# TSC_AD7843.net
KiCad netlist of a schematic drawn in Altium Designer
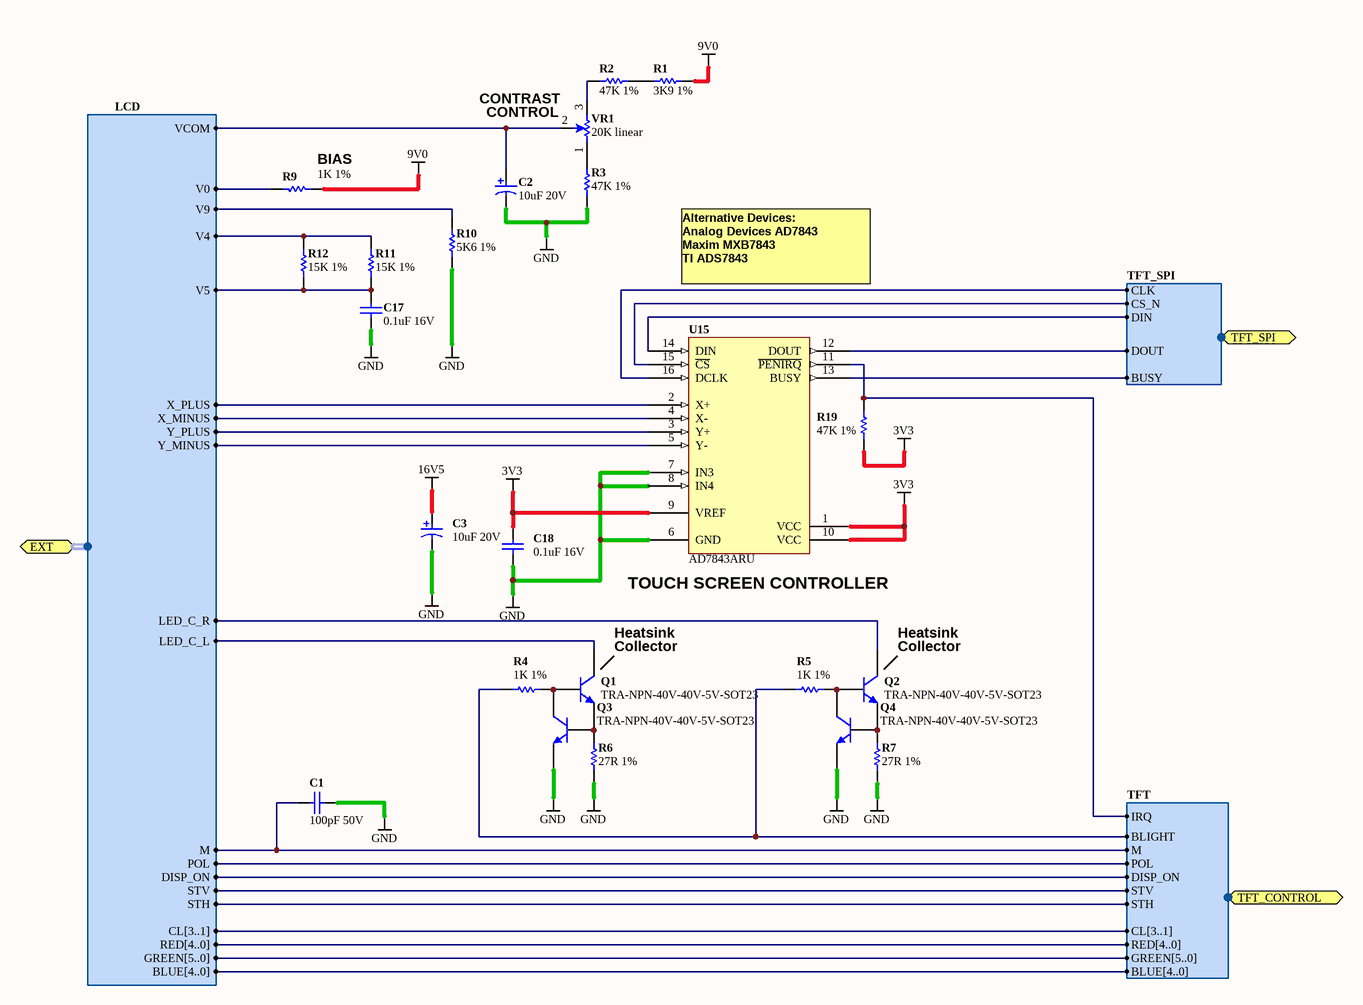
[diagram p0: TSC_AD7843.SchDoc]

(export (version "E")
  (design (tool "Eeschema 10.0.6"))
  (components
    (comp (ref "C1")
      (value "100pF 50V")
      (footprint "CAPC1005-STAR")
      (description "Capacitor, Ceramic, 100pF 5% 50V 0402 (1005) COG")
      (fields (field (name "TOLERANCE") "5 %"))
      (libsource (lib "altium-import") (part "root_3_mirrored_CAP-NP_"))
    )
    (comp (ref "C2")
      (value "10uF 20V")
      (footprint "CAPC3528-STAR")
      (description "Capacitor, Tantalum, 10uF 10% 20V MCCT-B (3528)")
      (fields (field (name "TOLERANCE") "10 %"))
      (libsource (lib "altium-import") (part "root_0_CAP-P_"))
    )
    (comp (ref "C3")
      (value "10uF 20V")
      (footprint "CAPC3528-STAR")
      (description "Capacitor, Tantalum, 10uF 10% 20V MCCT-B (3528)")
      (fields (field (name "TOLERANCE") "10 %"))
      (libsource (lib "altium-import") (part "root_0_CAP-P_"))
    )
    (comp (ref "C17")
      (value "0.1uF 16V")
      (footprint "CAPC1005-STAR")
      (description "Capacitor, Ceramic, 0.1uF 10% 16V 0402 (1005) X7R")
      (fields (field (name "TOLERANCE") "10 %"))
      (libsource (lib "altium-import") (part "root_0_mirrored_CAP-NP_"))
    )
    (comp (ref "C18")
      (value "0.1uF 16V")
      (footprint "CAPC1005-STAR")
      (description "Capacitor, Ceramic, 0.1uF 10% 16V 0402 (1005) X7R")
      (fields (field (name "TOLERANCE") "10 %"))
      (libsource (lib "altium-import") (part "root_0_CAP-NP_"))
    )
    (comp (ref "Q1")
      (value "TRA-NPN-40V-40V-5V-SOT23")
      (footprint "SOT95P230-3C")
      (description "Transistor, FMMT491A Small Signal NPN")
      (libsource (lib "altium-import") (part "root_0_TRA-NPN_"))
    )
    (comp (ref "Q2")
      (value "TRA-NPN-40V-40V-5V-SOT23")
      (footprint "SOT95P230-3C")
      (description "Transistor, FMMT491A Small Signal NPN")
      (libsource (lib "altium-import") (part "root_0_TRA-NPN_"))
    )
    (comp (ref "Q3")
      (value "TRA-NPN-40V-40V-5V-SOT23")
      (footprint "SOT95P230-3C")
      (description "Transistor, FMMT491A Small Signal NPN")
      (libsource (lib "altium-import") (part "root_0_mirrored_TRA-NPN_"))
    )
    (comp (ref "Q4")
      (value "TRA-NPN-40V-40V-5V-SOT23")
      (footprint "SOT95P230-3C")
      (description "Transistor, FMMT491A Small Signal NPN")
      (libsource (lib "altium-import") (part "root_0_mirrored_TRA-NPN_"))
    )
    (comp (ref "R1")
      (value "3K9 1%")
      (footprint "RESC1005-STAR")
      (description "Resistor, 3K9 1% 0402 (1005)")
      (fields (field (name "TOLERANCE") "1 %"))
      (libsource (lib "altium-import") (part "root_1_RES_"))
    )
    (comp (ref "R2")
      (value "47K 1%")
      (footprint "RESC1005-STAR")
      (description "Resistor, 47K 1% 0402 (1005)")
      (fields (field (name "TOLERANCE") "1 %"))
      (libsource (lib "altium-import") (part "root_1_RES_"))
    )
    (comp (ref "R3")
      (value "47K 1%")
      (footprint "RESC1005-STAR")
      (description "Resistor, 47K 1% 0402 (1005)")
      (fields (field (name "TOLERANCE") "1 %"))
      (libsource (lib "altium-import") (part "root_2_RES_"))
    )
    (comp (ref "R4")
      (value "1K 1%")
      (footprint "RESC1005-STAR")
      (description "Resistor, 1K 1% 0402 (1005)")
      (fields (field (name "TOLERANCE") "1 %"))
      (libsource (lib "altium-import") (part "root_1_RES_"))
    )
    (comp (ref "R5")
      (value "1K 1%")
      (footprint "RESC1005-STAR")
      (description "Resistor, 1K 1% 0402 (1005)")
      (fields (field (name "TOLERANCE") "1 %"))
      (libsource (lib "altium-import") (part "root_1_RES_"))
    )
    (comp (ref "R6")
      (value "27R 1%")
      (footprint "RESC1005-STAR")
      (description "Resistor, 27R 1% 0402 (1005)")
      (fields (field (name "TOLERANCE") "1 %"))
      (libsource (lib "altium-import") (part "root_2_RES_"))
    )
    (comp (ref "R7")
      (value "27R 1%")
      (footprint "RESC1005-STAR")
      (description "Resistor, 27R 1% 0402 (1005)")
      (fields (field (name "TOLERANCE") "1 %"))
      (libsource (lib "altium-import") (part "root_2_RES_"))
    )
    (comp (ref "R9")
      (value "1K 1%")
      (footprint "RESC1005-STAR")
      (description "Resistor, 1K 1% 0402 (1005)")
      (fields (field (name "TOLERANCE") "1 %"))
      (libsource (lib "altium-import") (part "root_3_mirrored_RES_"))
    )
    (comp (ref "R10")
      (value "5K6 1%")
      (footprint "RESC1005-STAR")
      (description "Resistor, 5K6 1% 0402 (1005)")
      (fields (field (name "TOLERANCE") "1 %"))
      (libsource (lib "altium-import") (part "root_2_RES_"))
    )
    (comp (ref "R11")
      (value "15K 1%")
      (footprint "RESC1005-STAR")
      (description "Resistor, 15K 1% 0402 (1005)")
      (fields (field (name "TOLERANCE") "1 %"))
      (libsource (lib "altium-import") (part "root_2_RES_"))
    )
    (comp (ref "R12")
      (value "15K 1%")
      (footprint "RESC1005-STAR")
      (description "Resistor, 15K 1% 0402 (1005)")
      (fields (field (name "TOLERANCE") "1 %"))
      (libsource (lib "altium-import") (part "root_2_RES_"))
    )
    (comp (ref "R19")
      (value "47K 1%")
      (footprint "RESC1005-STAR")
      (description "Resistor, 47K 1% 0402 (1005)")
      (fields (field (name "TOLERANCE") "1 %"))
      (libsource (lib "altium-import") (part "root_0_RES_"))
    )
    (comp (ref "U15")
      (value "AD7843ARU")
      (footprint "TSOP65P638-16")
      (description "AD7843ARU,12-bit SPI Touch Screen Digitizer")
      (libsource (lib "altium-import") (part "root_0_AD7843ARU_"))
    )
    (comp (ref "VR1")
      (value "20K linear")
      (footprint "TRIM_3314J-1-203E")
      (description "Potentiometer, 20K 4mm Cermet PCB SMT Trimmer")
      (libsource (lib "altium-import") (part "root_2_mirrored_POT_"))
    )
  )
  (nets
    (net (code "5") (name "/BLIGHT") (class "Default")
      (node (ref "R4") (pin "1") (pinfunction "1_1") (pintype "passive"))
      (node (ref "R5") (pin "1") (pinfunction "1_1") (pintype "passive"))
    )
    (net (code "6") (name "/BUSY") (class "Default")
      (node (ref "U15") (pin "13") (pinfunction "BUSY_13") (pintype "output"))
    )
    (net (code "7") (name "/CLK") (class "Default")
      (node (ref "U15") (pin "16") (pinfunction "DCLK_16") (pintype "input"))
    )
    (net (code "8") (name "/CS_N") (class "Default")
      (node (ref "U15") (pin "15") (pinfunction "~{CS}_15") (pintype "input"))
    )
    (net (code "9") (name "/DIN") (class "Default")
      (node (ref "U15") (pin "14") (pinfunction "DIN_14") (pintype "input"))
    )
    (net (code "11") (name "/DOUT") (class "Default")
      (node (ref "U15") (pin "12") (pinfunction "DOUT_12") (pintype "output"))
    )
    (net (code "12") (name "/IRQ") (class "Default")
      (node (ref "R19") (pin "1") (pinfunction "1_1") (pintype "passive"))
      (node (ref "U15") (pin "11") (pinfunction "~{PENIRQ}_11") (pintype "output"))
    )
    (net (code "13") (name "/LED_C_L") (class "Default")
      (node (ref "Q1") (pin "3") (pinfunction "C_3") (pintype "passive"))
    )
    (net (code "14") (name "/LED_C_R") (class "Default")
      (node (ref "Q2") (pin "3") (pinfunction "C_3") (pintype "passive"))
    )
    (net (code "15") (name "/M") (class "Default")
      (node (ref "C1") (pin "1") (pinfunction "1_1") (pintype "passive"))
    )
    (net (code "20") (name "/V0") (class "Default")
      (node (ref "R9") (pin "1") (pinfunction "1_1") (pintype "passive"))
    )
    (net (code "21") (name "/V4") (class "Default")
      (node (ref "R11") (pin "2") (pinfunction "2_2") (pintype "passive"))
      (node (ref "R12") (pin "2") (pinfunction "2_2") (pintype "passive"))
    )
    (net (code "22") (name "/V5") (class "Default")
      (node (ref "C17") (pin "1") (pinfunction "1_1") (pintype "passive"))
      (node (ref "R11") (pin "1") (pinfunction "1_1") (pintype "passive"))
      (node (ref "R12") (pin "1") (pinfunction "1_1") (pintype "passive"))
    )
    (net (code "23") (name "/V9") (class "Default")
      (node (ref "R10") (pin "2") (pinfunction "2_2") (pintype "passive"))
    )
    (net (code "24") (name "/VCOM") (class "Default")
      (node (ref "C2") (pin "1") (pinfunction "1_1") (pintype "passive"))
      (node (ref "VR1") (pin "2") (pinfunction "2_2") (pintype "passive"))
    )
    (net (code "25") (name "/X_MINUS") (class "Default")
      (node (ref "U15") (pin "4") (pinfunction "X-_4") (pintype "input"))
    )
    (net (code "26") (name "/X_PLUS") (class "Default")
      (node (ref "U15") (pin "2") (pinfunction "X+_2") (pintype "input"))
    )
    (net (code "27") (name "/Y_MINUS") (class "Default")
      (node (ref "U15") (pin "5") (pinfunction "Y-_5") (pintype "input"))
    )
    (net (code "28") (name "/Y_PLUS") (class "Default")
      (node (ref "U15") (pin "3") (pinfunction "Y+_3") (pintype "input"))
    )
    (net (code "32") (name "3V3") (class "Default")
      (node (ref "C18") (pin "1") (pinfunction "1_1") (pintype "passive"))
      (node (ref "R19") (pin "2") (pinfunction "2_2") (pintype "passive"))
      (node (ref "U15") (pin "1") (pinfunction "VCC_1") (pintype "power_in"))
      (node (ref "U15") (pin "10") (pinfunction "VCC_10") (pintype "power_in"))
      (node (ref "U15") (pin "9") (pinfunction "VREF_9") (pintype "passive"))
    )
    (net (code "33") (name "9V0") (class "Default")
      (node (ref "R1") (pin "2") (pinfunction "2_2") (pintype "passive"))
      (node (ref "R9") (pin "2") (pinfunction "2_2") (pintype "passive"))
    )
    (net (code "34") (name "16V5") (class "Default")
      (node (ref "C3") (pin "1") (pinfunction "1_1") (pintype "passive"))
    )
    (net (code "35") (name "GND") (class "Default")
      (node (ref "C1") (pin "2") (pinfunction "2_2") (pintype "passive"))
      (node (ref "C17") (pin "2") (pinfunction "2_2") (pintype "passive"))
      (node (ref "C18") (pin "2") (pinfunction "2_2") (pintype "passive"))
      (node (ref "C2") (pin "2") (pinfunction "2_2") (pintype "passive"))
      (node (ref "C3") (pin "2") (pinfunction "2_2") (pintype "passive"))
      (node (ref "Q3") (pin "2") (pinfunction "E_2") (pintype "passive"))
      (node (ref "Q4") (pin "2") (pinfunction "E_2") (pintype "passive"))
      (node (ref "R10") (pin "1") (pinfunction "1_1") (pintype "passive"))
      (node (ref "R3") (pin "1") (pinfunction "1_1") (pintype "passive"))
      (node (ref "R6") (pin "1") (pinfunction "1_1") (pintype "passive"))
      (node (ref "R7") (pin "1") (pinfunction "1_1") (pintype "passive"))
      (node (ref "U15") (pin "6") (pinfunction "GND_6") (pintype "power_in"))
      (node (ref "U15") (pin "7") (pinfunction "IN3_7") (pintype "input"))
      (node (ref "U15") (pin "8") (pinfunction "IN4_8") (pintype "input"))
    )
    (net (code "36") (name "Net-(Q1-B)") (class "Default")
      (node (ref "Q1") (pin "1") (pinfunction "B_1") (pintype "passive"))
      (node (ref "Q3") (pin "3") (pinfunction "C_3") (pintype "passive"))
      (node (ref "R4") (pin "2") (pinfunction "2_2") (pintype "passive"))
    )
    (net (code "37") (name "Net-(Q1-E)") (class "Default")
      (node (ref "Q1") (pin "2") (pinfunction "E_2") (pintype "passive"))
      (node (ref "Q3") (pin "1") (pinfunction "B_1") (pintype "passive"))
      (node (ref "R6") (pin "2") (pinfunction "2_2") (pintype "passive"))
    )
    (net (code "38") (name "Net-(Q2-B)") (class "Default")
      (node (ref "Q2") (pin "1") (pinfunction "B_1") (pintype "passive"))
      (node (ref "Q4") (pin "3") (pinfunction "C_3") (pintype "passive"))
      (node (ref "R5") (pin "2") (pinfunction "2_2") (pintype "passive"))
    )
    (net (code "39") (name "Net-(Q2-E)") (class "Default")
      (node (ref "Q2") (pin "2") (pinfunction "E_2") (pintype "passive"))
      (node (ref "Q4") (pin "1") (pinfunction "B_1") (pintype "passive"))
      (node (ref "R7") (pin "2") (pinfunction "2_2") (pintype "passive"))
    )
    (net (code "40") (name "Net-(R1-Pad1)") (class "Default")
      (node (ref "R1") (pin "1") (pinfunction "1_1") (pintype "passive"))
      (node (ref "R2") (pin "2") (pinfunction "2_2") (pintype "passive"))
    )
    (net (code "41") (name "Net-(R2-Pad1)") (class "Default")
      (node (ref "R2") (pin "1") (pinfunction "1_1") (pintype "passive"))
      (node (ref "VR1") (pin "3") (pinfunction "3_3") (pintype "passive"))
    )
    (net (code "42") (name "Net-(R3-Pad2)") (class "Default")
      (node (ref "R3") (pin "2") (pinfunction "2_2") (pintype "passive"))
      (node (ref "VR1") (pin "1") (pinfunction "1_1") (pintype "passive"))
    )
  )
)
